# FILTER.net
KiCad netlist of a schematic drawn in Altium Designer
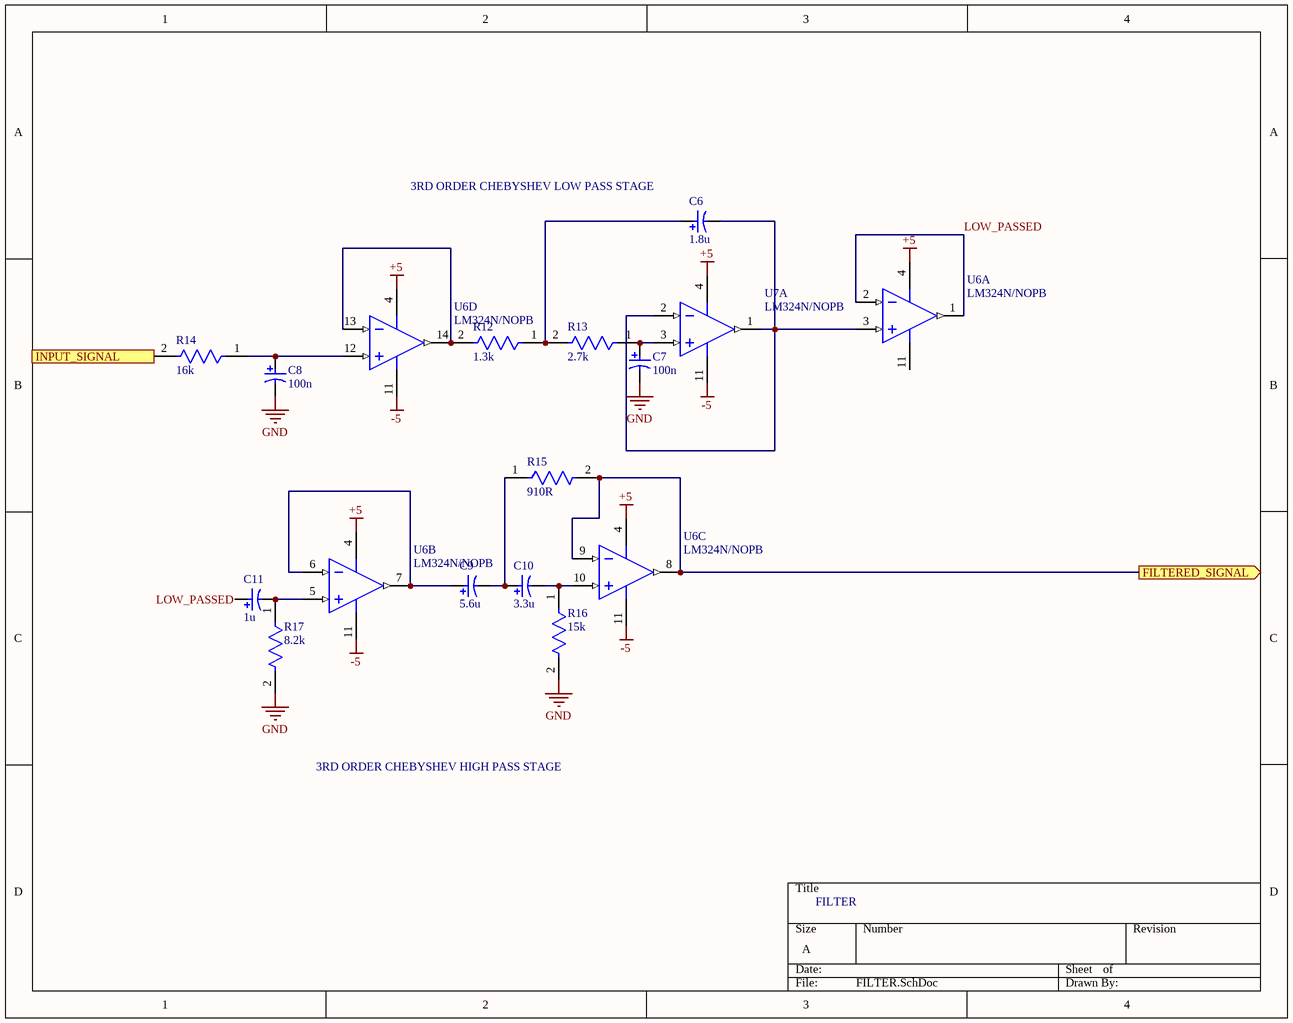
[diagram p0: FILTER.SchDoc]

(export (version "E")
  (design (tool "Eeschema 10.0.6"))
  (components
    (comp (ref "C6")
      (value "1.8u")
      (footprint "PNSC-ECA-1VM221-2")
      (description "Aluminum Electrolytic Capacitor, 220 uF, +/- 20%, 35 V, -40 to 85 degC, 2-Pin THD, RoHS, Bulk")
      (fields (field (name "MANUFACTURER") "Panasonic"))
      (libsource (lib "Altium Content Vault") (part "CAP-P-2"))
    )
    (comp (ref "C7")
      (value "100n")
      (footprint "PNSC-ECA-1VM221-2")
      (description "Aluminum Electrolytic Capacitor, 220 uF, +/- 20%, 35 V, -40 to 85 degC, 2-Pin THD, RoHS, Bulk")
      (fields (field (name "MANUFACTURER") "Panasonic"))
      (libsource (lib "Altium Content Vault") (part "CAP-P-2"))
    )
    (comp (ref "C8")
      (value "100n")
      (footprint "PNSC-ECA-1VM221-2")
      (description "Aluminum Electrolytic Capacitor, 220 uF, +/- 20%, 35 V, -40 to 85 degC, 2-Pin THD, RoHS, Bulk")
      (fields (field (name "MANUFACTURER") "Panasonic"))
      (libsource (lib "Altium Content Vault") (part "CAP-P-2"))
    )
    (comp (ref "C9")
      (value "5.6u")
      (footprint "PNSC-ECA-1VM221-2")
      (description "Aluminum Electrolytic Capacitor, 220 uF, +/- 20%, 35 V, -40 to 85 degC, 2-Pin THD, RoHS, Bulk")
      (fields (field (name "MANUFACTURER") "Panasonic"))
      (libsource (lib "Altium Content Vault") (part "CAP-P-2"))
    )
    (comp (ref "C10")
      (value "3.3u")
      (footprint "PNSC-ECA-1VM221-2")
      (description "Aluminum Electrolytic Capacitor, 220 uF, +/- 20%, 35 V, -40 to 85 degC, 2-Pin THD, RoHS, Bulk")
      (fields (field (name "MANUFACTURER") "Panasonic"))
      (libsource (lib "Altium Content Vault") (part "CAP-P-2"))
    )
    (comp (ref "C11")
      (value "1u")
      (footprint "PNSC-ECA-1VM221-2")
      (description "Aluminum Electrolytic Capacitor, 220 uF, +/- 20%, 35 V, -40 to 85 degC, 2-Pin THD, RoHS, Bulk")
      (fields (field (name "MANUFACTURER") "Panasonic"))
      (libsource (lib "Altium Content Vault") (part "CAP-P-2"))
    )
    (comp (ref "R12")
      (value "1.3k")
      (footprint "FP-CF18-MFG")
      (description "RES 2.2K OHM 1/8W 5% CF AXIAL")
      (fields
        (field (name "OCTOPART") "https://octopart.com/cf18jt2k20-stackpole+electronics-19205714")
        (field (name "TOLERANCE") "5%")
      )
      (libsource (lib "Altium Content Vault") (part "1029c3af85768c4190bb7ad29bc67b5"))
    )
    (comp (ref "R13")
      (value "2.7k")
      (footprint "FP-CF18-MFG")
      (description "RES 2.2K OHM 1/8W 5% CF AXIAL")
      (fields
        (field (name "OCTOPART") "https://octopart.com/cf18jt2k20-stackpole+electronics-19205714")
        (field (name "TOLERANCE") "5%")
      )
      (libsource (lib "Altium Content Vault") (part "1029c3af85768c4190bb7ad29bc67b5"))
    )
    (comp (ref "R14")
      (value "16k")
      (footprint "FP-CF18-MFG")
      (description "RES 2.2K OHM 1/8W 5% CF AXIAL")
      (fields
        (field (name "OCTOPART") "https://octopart.com/cf18jt2k20-stackpole+electronics-19205714")
        (field (name "TOLERANCE") "5%")
      )
      (libsource (lib "Altium Content Vault") (part "1029c3af85768c4190bb7ad29bc67b5"))
    )
    (comp (ref "R15")
      (value "910R")
      (footprint "FP-CF18-MFG")
      (description "RES 2.2K OHM 1/8W 5% CF AXIAL")
      (fields
        (field (name "OCTOPART") "https://octopart.com/cf18jt2k20-stackpole+electronics-19205714")
        (field (name "TOLERANCE") "5%")
      )
      (libsource (lib "Altium Content Vault") (part "1029c3af85768c4190bb7ad29bc67b5"))
    )
    (comp (ref "R16")
      (value "15k")
      (footprint "FP-CF18-MFG")
      (description "RES 2.2K OHM 1/8W 5% CF AXIAL")
      (fields
        (field (name "OCTOPART") "https://octopart.com/cf18jt2k20-stackpole+electronics-19205714")
        (field (name "TOLERANCE") "5%")
      )
      (libsource (lib "Altium Content Vault") (part "1029c3af85768c4190bb7ad29bc67b5"))
    )
    (comp (ref "R17")
      (value "8.2k")
      (footprint "FP-CF18-MFG")
      (description "RES 2.2K OHM 1/8W 5% CF AXIAL")
      (fields
        (field (name "OCTOPART") "https://octopart.com/cf18jt2k20-stackpole+electronics-19205714")
        (field (name "TOLERANCE") "5%")
      )
      (libsource (lib "Altium Content Vault") (part "1029c3af85768c4190bb7ad29bc67b5"))
    )
    (comp (ref "U6")
      (value "LM324N/NOPB")
      (footprint "NFF0014A")
      (description "Low Power Quad Operational Amplifier, 14-pin MDIP, Pb-Free")
      (fields (field (name "MANUFACTURER") "Texas Instruments"))
      (libsource (lib "Altium Content Vault") (part "AMP-OPA-LM124-14"))
    )
    (comp (ref "U7")
      (value "LM324N/NOPB")
      (footprint "NFF0014A")
      (description "Low Power Quad Operational Amplifier, 14-pin MDIP, Pb-Free")
      (fields (field (name "MANUFACTURER") "Texas Instruments"))
      (libsource (lib "Altium Content Vault") (part "AMP-OPA-LM124-14"))
    )
  )
  (nets
    (net (code "1") (name "+5") (class "Default")
      (node (ref "U6") (pin "4") (pinfunction "V+_4") (pintype "power_in"))
      (node (ref "U7") (pin "4") (pinfunction "V+_4") (pintype "power_in"))
    )
    (net (code "2") (name "-5") (class "Default")
      (node (ref "U6") (pin "11") (pinfunction "GND_11") (pintype "power_in"))
      (node (ref "U7") (pin "11") (pinfunction "GND_11") (pintype "power_in"))
    )
    (net (code "3") (name "/FILTERED_SIGNAL") (class "Default")
      (node (ref "R15") (pin "2") (pinfunction "2_2") (pintype "passive"))
      (node (ref "U6") (pin "8") (pinfunction "OUT3_8") (pintype "output"))
      (node (ref "U6") (pin "9") (pinfunction "IN3-_9") (pintype "input"))
    )
    (net (code "4") (name "/INPUT_SIGNAL") (class "Default")
      (node (ref "R14") (pin "2") (pinfunction "2_2") (pintype "passive"))
    )
    (net (code "5") (name "/LOW_PASSED") (class "Default")
      (node (ref "C11") (pin "1") (pinfunction "1_1") (pintype "passive"))
      (node (ref "U6") (pin "1") (pinfunction "OUT1_1") (pintype "output"))
      (node (ref "U6") (pin "2") (pinfunction "IN1-_2") (pintype "input"))
    )
    (net (code "6") (name "GND") (class "Default")
      (node (ref "C7") (pin "2") (pinfunction "2_2") (pintype "passive"))
      (node (ref "C8") (pin "2") (pinfunction "2_2") (pintype "passive"))
      (node (ref "R16") (pin "2") (pinfunction "2_2") (pintype "passive"))
      (node (ref "R17") (pin "2") (pinfunction "2_2") (pintype "passive"))
    )
    (net (code "7") (name "Net-(C6-Pad1)") (class "Default")
      (node (ref "C6") (pin "1") (pinfunction "1_1") (pintype "passive"))
      (node (ref "R12") (pin "1") (pinfunction "1_1") (pintype "passive"))
      (node (ref "R13") (pin "2") (pinfunction "2_2") (pintype "passive"))
    )
    (net (code "8") (name "Net-(C10-Pad1)") (class "Default")
      (node (ref "C10") (pin "1") (pinfunction "1_1") (pintype "passive"))
      (node (ref "C9") (pin "2") (pinfunction "2_2") (pintype "passive"))
      (node (ref "R15") (pin "1") (pinfunction "1_1") (pintype "passive"))
    )
    (net (code "9") (name "Net-(U6A-IN1+)") (class "Default")
      (node (ref "C6") (pin "2") (pinfunction "2_2") (pintype "passive"))
      (node (ref "U6") (pin "3") (pinfunction "IN1+_3") (pintype "input"))
      (node (ref "U7") (pin "1") (pinfunction "OUT1_1") (pintype "output"))
      (node (ref "U7") (pin "2") (pinfunction "IN1-_2") (pintype "input"))
    )
    (net (code "10") (name "Net-(U6B-IN2+)") (class "Default")
      (node (ref "C11") (pin "2") (pinfunction "2_2") (pintype "passive"))
      (node (ref "R17") (pin "1") (pinfunction "1_1") (pintype "passive"))
      (node (ref "U6") (pin "5") (pinfunction "IN2+_5") (pintype "input"))
    )
    (net (code "11") (name "Net-(U6B-IN2-)") (class "Default")
      (node (ref "C9") (pin "1") (pinfunction "1_1") (pintype "passive"))
      (node (ref "U6") (pin "6") (pinfunction "IN2-_6") (pintype "input"))
      (node (ref "U6") (pin "7") (pinfunction "OUT2_7") (pintype "output"))
    )
    (net (code "12") (name "Net-(U6C-IN3+)") (class "Default")
      (node (ref "C10") (pin "2") (pinfunction "2_2") (pintype "passive"))
      (node (ref "R16") (pin "1") (pinfunction "1_1") (pintype "passive"))
      (node (ref "U6") (pin "10") (pinfunction "IN3+_10") (pintype "input"))
    )
    (net (code "13") (name "Net-(U6D-IN4+)") (class "Default")
      (node (ref "C8") (pin "1") (pinfunction "1_1") (pintype "passive"))
      (node (ref "R14") (pin "1") (pinfunction "1_1") (pintype "passive"))
      (node (ref "U6") (pin "12") (pinfunction "IN4+_12") (pintype "input"))
    )
    (net (code "14") (name "Net-(U6D-IN4-)") (class "Default")
      (node (ref "R12") (pin "2") (pinfunction "2_2") (pintype "passive"))
      (node (ref "U6") (pin "13") (pinfunction "IN4-_13") (pintype "input"))
      (node (ref "U6") (pin "14") (pinfunction "OUT4_14") (pintype "output"))
    )
    (net (code "15") (name "Net-(U7A-IN1+)") (class "Default")
      (node (ref "C7") (pin "1") (pinfunction "1_1") (pintype "passive"))
      (node (ref "R13") (pin "1") (pinfunction "1_1") (pintype "passive"))
      (node (ref "U7") (pin "3") (pinfunction "IN1+_3") (pintype "input"))
    )
    (net (code "16") (name "unconnected-(U6A-GND-Pad11)") (class "Default")
      (node (ref "U6") (pin "11") (pinfunction "GND_11") (pintype "power_in"))
    )
  )
)
